# ESP_SIM7000V1_62.net
KiCad netlist of a schematic drawn in EAGLE
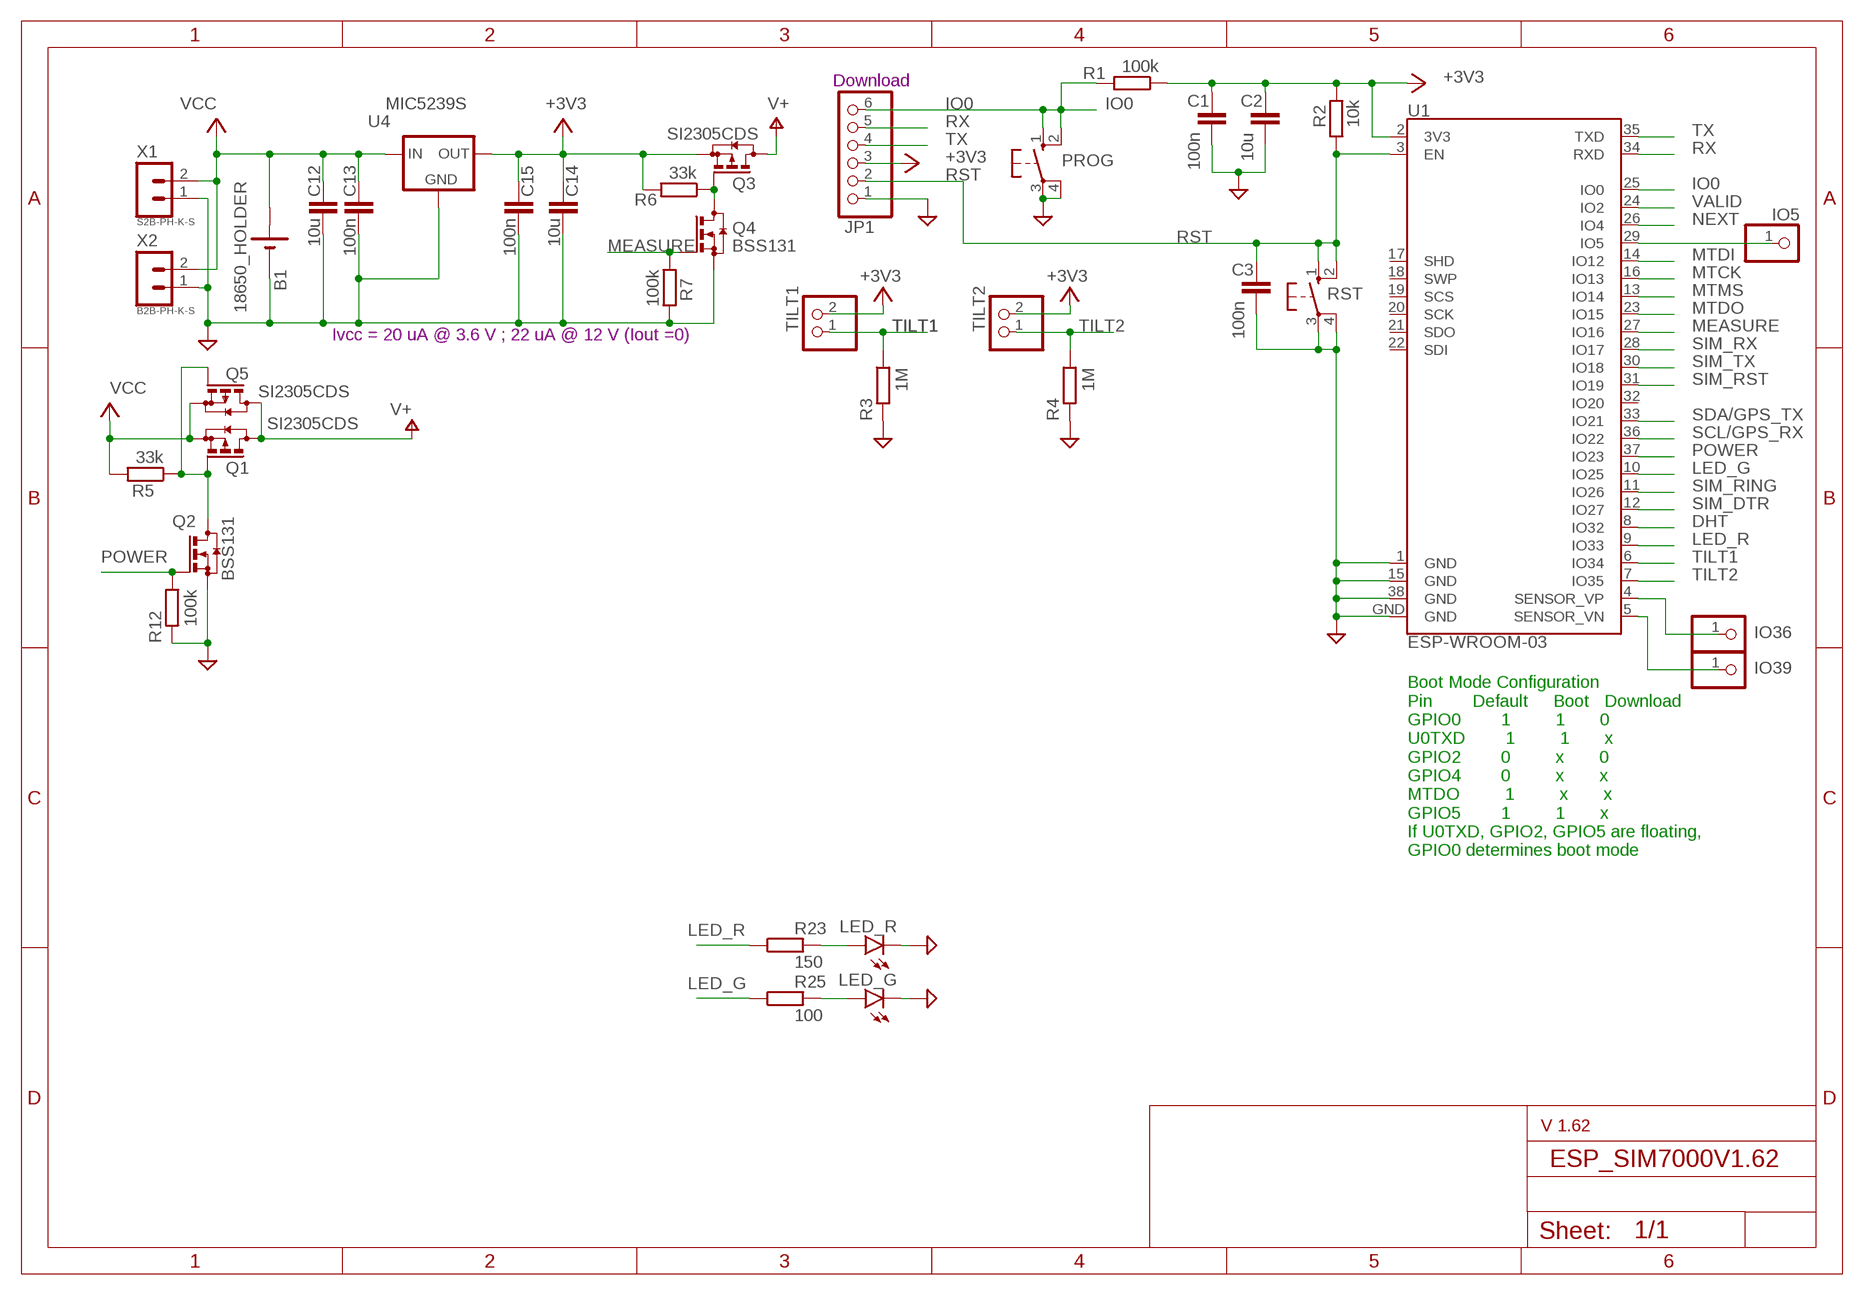
[diagram p0: schematic, sheet 1]

(export (version "E")
  (design (tool "Eeschema 10.0.6"))
  (components
    (comp (ref "B1")
      (value "18650_HOLDER")
      (footprint "eagle-import:18650")
      (libsource (lib "eagle-import") (part "18650_HOLDER"))
    )
    (comp (ref "C1")
      (value "100n")
      (footprint "eagle-import:C1206")
      (libsource (lib "eagle-import") (part "CC1206"))
    )
    (comp (ref "C2")
      (value "10u")
      (footprint "eagle-import:C1210")
      (libsource (lib "eagle-import") (part "CC1210"))
    )
    (comp (ref "C3")
      (value "100n")
      (footprint "eagle-import:C1206")
      (libsource (lib "eagle-import") (part "CC1206"))
    )
    (comp (ref "C12")
      (value "10u")
      (footprint "eagle-import:C1210")
      (libsource (lib "eagle-import") (part "CC1210"))
    )
    (comp (ref "C13")
      (value "100n")
      (footprint "eagle-import:C1206")
      (libsource (lib "eagle-import") (part "CC1206"))
    )
    (comp (ref "C14")
      (value "10u")
      (footprint "eagle-import:C1210")
      (libsource (lib "eagle-import") (part "CC1210"))
    )
    (comp (ref "C15")
      (value "100n")
      (footprint "eagle-import:C1206")
      (libsource (lib "eagle-import") (part "CC1206"))
    )
    (comp (ref "IO5")
      (value "PINHD-1X1")
      (footprint "eagle-import:1X01")
      (libsource (lib "eagle-import") (part "PINHD-1X1"))
    )
    (comp (ref "IO36")
      (value "PINHD-1X1")
      (footprint "eagle-import:1X01")
      (libsource (lib "eagle-import") (part "PINHD-1X1"))
    )
    (comp (ref "IO39")
      (value "PINHD-1X1")
      (footprint "eagle-import:1X01")
      (libsource (lib "eagle-import") (part "PINHD-1X1"))
    )
    (comp (ref "JP1")
      (value "PINHD-1X6")
      (footprint "eagle-import:1X06")
      (libsource (lib "eagle-import") (part "PINHD-1X6"))
    )
    (comp (ref "LED_G")
      (value "LEDSMT1206")
      (footprint "eagle-import:1206")
      (libsource (lib "eagle-import") (part "LEDSMT1206"))
    )
    (comp (ref "LED_R")
      (value "LEDSMT1206")
      (footprint "eagle-import:1206")
      (libsource (lib "eagle-import") (part "LEDSMT1206"))
    )
    (comp (ref "PROG")
      (value "10-XX")
      (footprint "eagle-import:B3F-10XX")
      (fields (field (name "MPN") "B3F-1000"))
      (libsource (lib "eagle-import") (part "10-XX"))
    )
    (comp (ref "Q1")
      (value "SI2305CDS")
      (footprint "eagle-import:SOT23")
      (libsource (lib "eagle-import") (part "SI2305CDS"))
    )
    (comp (ref "Q2")
      (value "BSS131")
      (footprint "eagle-import:SOT23")
      (libsource (lib "eagle-import") (part "BSS131"))
    )
    (comp (ref "Q3")
      (value "SI2305CDS")
      (footprint "eagle-import:SOT23")
      (libsource (lib "eagle-import") (part "SI2305CDS"))
    )
    (comp (ref "Q4")
      (value "BSS131")
      (footprint "eagle-import:SOT23")
      (libsource (lib "eagle-import") (part "BSS131"))
    )
    (comp (ref "Q5")
      (value "SI2305CDS")
      (footprint "eagle-import:SOT23")
      (libsource (lib "eagle-import") (part "SI2305CDS"))
    )
    (comp (ref "R1")
      (value "100k")
      (footprint "eagle-import:R1206")
      (libsource (lib "eagle-import") (part "RR1206"))
    )
    (comp (ref "R2")
      (value "10k")
      (footprint "eagle-import:R1206")
      (libsource (lib "eagle-import") (part "RR1206"))
    )
    (comp (ref "R3")
      (value "1M")
      (footprint "eagle-import:R1206")
      (libsource (lib "eagle-import") (part "RR1206"))
    )
    (comp (ref "R4")
      (value "1M")
      (footprint "eagle-import:R1206")
      (libsource (lib "eagle-import") (part "RR1206"))
    )
    (comp (ref "R5")
      (value "33k")
      (footprint "eagle-import:R1206")
      (libsource (lib "eagle-import") (part "RR1206"))
    )
    (comp (ref "R6")
      (value "33k")
      (footprint "eagle-import:R1206")
      (libsource (lib "eagle-import") (part "RR1206"))
    )
    (comp (ref "R7")
      (value "100k")
      (footprint "eagle-import:R1206")
      (libsource (lib "eagle-import") (part "RR1206"))
    )
    (comp (ref "R12")
      (value "100k")
      (footprint "eagle-import:R1206")
      (libsource (lib "eagle-import") (part "RR1206"))
    )
    (comp (ref "R23")
      (value "150")
      (footprint "eagle-import:R1206")
      (libsource (lib "eagle-import") (part "RR1206"))
    )
    (comp (ref "R25")
      (value "100")
      (footprint "eagle-import:R1206")
      (libsource (lib "eagle-import") (part "RR1206"))
    )
    (comp (ref "RST")
      (value "10-XX")
      (footprint "eagle-import:B3F-10XX")
      (fields (field (name "MPN") "B3F-1000"))
      (libsource (lib "eagle-import") (part "10-XX"))
    )
    (comp (ref "TILT1")
      (value "PINHD-1X2")
      (footprint "eagle-import:1X02")
      (libsource (lib "eagle-import") (part "PINHD-1X2"))
    )
    (comp (ref "TILT2")
      (value "PINHD-1X2")
      (footprint "eagle-import:1X02")
      (libsource (lib "eagle-import") (part "PINHD-1X2"))
    )
    (comp (ref "U1")
      (value "ESP-WROOM-03")
      (footprint "eagle-import:ESP-WROOM-03")
      (libsource (lib "eagle-import") (part "ESP-WROOM-03"))
    )
    (comp (ref "U4")
      (value "MIC5239S")
      (footprint "eagle-import:SOT223")
      (libsource (lib "eagle-import") (part "MIC5239S"))
    )
    (comp (ref "X1")
      (value "S2B-PH-K-S")
      (footprint "eagle-import:S2B-PH-K-S")
      (libsource (lib "eagle-import") (part "S2B-PH-K-S"))
    )
    (comp (ref "X2")
      (value "B2B-PH-K-S")
      (footprint "eagle-import:B2B-PH-K-S")
      (libsource (lib "eagle-import") (part "B2B-PH-K-S"))
    )
  )
  (nets
    (net (code "1") (name "+3V3") (class "Default")
      (node (ref "C1") (pin "1") (pinfunction "1_1") (pintype "passive"))
      (node (ref "C14") (pin "1") (pinfunction "1_1") (pintype "passive"))
      (node (ref "C15") (pin "1") (pinfunction "1_1") (pintype "passive"))
      (node (ref "C2") (pin "1") (pinfunction "1_1") (pintype "passive"))
      (node (ref "JP1") (pin "3") (pinfunction "3_3") (pintype "passive"))
      (node (ref "Q3") (pin "2") (pinfunction "S_2") (pintype "passive"))
      (node (ref "R1") (pin "1") (pinfunction "1_1") (pintype "passive"))
      (node (ref "R2") (pin "2") (pinfunction "2_2") (pintype "passive"))
      (node (ref "R6") (pin "2") (pinfunction "2_2") (pintype "passive"))
      (node (ref "TILT1") (pin "2") (pinfunction "2_2") (pintype "passive"))
      (node (ref "TILT2") (pin "2") (pinfunction "2_2") (pintype "passive"))
      (node (ref "U1") (pin "2") (pinfunction "3V3_2") (pintype "bidirectional"))
      (node (ref "U4") (pin "3") (pinfunction "OUT_3") (pintype "passive"))
    )
    (net (code "2") (name "/DHT") (class "Default")
      (node (ref "U1") (pin "8") (pinfunction "IO32_8") (pintype "bidirectional"))
    )
    (net (code "3") (name "/IO0") (class "Default")
      (node (ref "JP1") (pin "6") (pinfunction "6_6") (pintype "passive"))
      (node (ref "PROG") (pin "1") (pinfunction "S_1") (pintype "passive"))
      (node (ref "PROG") (pin "2") (pinfunction "S1_2") (pintype "passive"))
      (node (ref "R1") (pin "2") (pinfunction "2_2") (pintype "passive"))
      (node (ref "U1") (pin "25") (pinfunction "IO0_25") (pintype "bidirectional"))
    )
    (net (code "4") (name "/LED_G") (class "Default")
      (node (ref "R25") (pin "1") (pinfunction "1_1") (pintype "passive"))
      (node (ref "U1") (pin "10") (pinfunction "IO25_10") (pintype "bidirectional"))
    )
    (net (code "5") (name "/LED_R") (class "Default")
      (node (ref "R23") (pin "1") (pinfunction "1_1") (pintype "passive"))
      (node (ref "U1") (pin "9") (pinfunction "IO33_9") (pintype "bidirectional"))
    )
    (net (code "6") (name "/MEASURE") (class "Default")
      (node (ref "Q4") (pin "1") (pinfunction "G_1") (pintype "passive"))
      (node (ref "R7") (pin "1") (pinfunction "1_1") (pintype "passive"))
      (node (ref "U1") (pin "27") (pinfunction "IO16_27") (pintype "bidirectional"))
    )
    (net (code "7") (name "/MTCK") (class "Default")
      (node (ref "U1") (pin "16") (pinfunction "IO13_16") (pintype "bidirectional"))
    )
    (net (code "8") (name "/MTDI") (class "Default")
      (node (ref "U1") (pin "14") (pinfunction "IO12_14") (pintype "bidirectional"))
    )
    (net (code "9") (name "/MTDO") (class "Default")
      (node (ref "U1") (pin "23") (pinfunction "IO15_23") (pintype "bidirectional"))
    )
    (net (code "10") (name "/MTMS") (class "Default")
      (node (ref "U1") (pin "13") (pinfunction "IO14_13") (pintype "bidirectional"))
    )
    (net (code "11") (name "/NEXT") (class "Default")
      (node (ref "U1") (pin "26") (pinfunction "IO4_26") (pintype "bidirectional"))
    )
    (net (code "12") (name "/POWER") (class "Default")
      (node (ref "Q2") (pin "1") (pinfunction "G_1") (pintype "passive"))
      (node (ref "R12") (pin "1") (pinfunction "1_1") (pintype "passive"))
      (node (ref "U1") (pin "37") (pinfunction "IO23_37") (pintype "bidirectional"))
    )
    (net (code "13") (name "/RST") (class "Default")
      (node (ref "C3") (pin "1") (pinfunction "1_1") (pintype "passive"))
      (node (ref "JP1") (pin "2") (pinfunction "2_2") (pintype "passive"))
      (node (ref "R2") (pin "1") (pinfunction "1_1") (pintype "passive"))
      (node (ref "RST") (pin "1") (pinfunction "S_1") (pintype "passive"))
      (node (ref "RST") (pin "2") (pinfunction "S1_2") (pintype "passive"))
      (node (ref "U1") (pin "3") (pinfunction "EN_3") (pintype "bidirectional"))
    )
    (net (code "14") (name "/RX") (class "Default")
      (node (ref "JP1") (pin "5") (pinfunction "5_5") (pintype "passive"))
      (node (ref "U1") (pin "34") (pinfunction "RXD_34") (pintype "bidirectional"))
    )
    (net (code "15") (name "/SCL{slash}GPS_RX") (class "Default")
      (node (ref "U1") (pin "36") (pinfunction "IO22_36") (pintype "bidirectional"))
    )
    (net (code "16") (name "/SDA{slash}GPS_TX") (class "Default")
      (node (ref "U1") (pin "33") (pinfunction "IO21_33") (pintype "bidirectional"))
    )
    (net (code "17") (name "/SIM_DTR") (class "Default")
      (node (ref "U1") (pin "12") (pinfunction "IO27_12") (pintype "bidirectional"))
    )
    (net (code "18") (name "/SIM_RING") (class "Default")
      (node (ref "U1") (pin "11") (pinfunction "IO26_11") (pintype "bidirectional"))
    )
    (net (code "19") (name "/SIM_RST") (class "Default")
      (node (ref "U1") (pin "31") (pinfunction "IO19_31") (pintype "bidirectional"))
    )
    (net (code "20") (name "/SIM_RX") (class "Default")
      (node (ref "U1") (pin "28") (pinfunction "IO17_28") (pintype "bidirectional"))
    )
    (net (code "21") (name "/SIM_TX") (class "Default")
      (node (ref "U1") (pin "30") (pinfunction "IO18_30") (pintype "bidirectional"))
    )
    (net (code "22") (name "/TILT1") (class "Default")
      (node (ref "R3") (pin "1") (pinfunction "1_1") (pintype "passive"))
      (node (ref "TILT1") (pin "1") (pinfunction "1_1") (pintype "passive"))
      (node (ref "U1") (pin "6") (pinfunction "IO34_6") (pintype "bidirectional"))
    )
    (net (code "23") (name "/TILT2") (class "Default")
      (node (ref "R4") (pin "1") (pinfunction "1_1") (pintype "passive"))
      (node (ref "TILT2") (pin "1") (pinfunction "1_1") (pintype "passive"))
      (node (ref "U1") (pin "7") (pinfunction "IO35_7") (pintype "bidirectional"))
    )
    (net (code "24") (name "/TX") (class "Default")
      (node (ref "JP1") (pin "4") (pinfunction "4_4") (pintype "passive"))
      (node (ref "U1") (pin "35") (pinfunction "TXD_35") (pintype "bidirectional"))
    )
    (net (code "25") (name "/VALID") (class "Default")
      (node (ref "U1") (pin "24") (pinfunction "IO2_24") (pintype "bidirectional"))
    )
    (net (code "26") (name "GND") (class "Default")
      (node (ref "B1") (pin "-") (pinfunction "-_-") (pintype "passive"))
      (node (ref "C1") (pin "2") (pinfunction "2_2") (pintype "passive"))
      (node (ref "C12") (pin "2") (pinfunction "2_2") (pintype "passive"))
      (node (ref "C13") (pin "2") (pinfunction "2_2") (pintype "passive"))
      (node (ref "C14") (pin "2") (pinfunction "2_2") (pintype "passive"))
      (node (ref "C15") (pin "2") (pinfunction "2_2") (pintype "passive"))
      (node (ref "C2") (pin "2") (pinfunction "2_2") (pintype "passive"))
      (node (ref "C3") (pin "2") (pinfunction "2_2") (pintype "passive"))
      (node (ref "JP1") (pin "1") (pinfunction "1_1") (pintype "passive"))
      (node (ref "LED_G") (pin "C") (pinfunction "C_C") (pintype "passive"))
      (node (ref "LED_R") (pin "C") (pinfunction "C_C") (pintype "passive"))
      (node (ref "PROG") (pin "3") (pinfunction "P_3") (pintype "passive"))
      (node (ref "PROG") (pin "4") (pinfunction "P1_4") (pintype "passive"))
      (node (ref "Q2") (pin "2") (pinfunction "S_2") (pintype "passive"))
      (node (ref "Q4") (pin "2") (pinfunction "S_2") (pintype "passive"))
      (node (ref "R12") (pin "2") (pinfunction "2_2") (pintype "passive"))
      (node (ref "R3") (pin "2") (pinfunction "2_2") (pintype "passive"))
      (node (ref "R4") (pin "2") (pinfunction "2_2") (pintype "passive"))
      (node (ref "R7") (pin "2") (pinfunction "2_2") (pintype "passive"))
      (node (ref "RST") (pin "3") (pinfunction "P_3") (pintype "passive"))
      (node (ref "RST") (pin "4") (pinfunction "P1_4") (pintype "passive"))
      (node (ref "U1") (pin "1") (pinfunction "GND_1") (pintype "bidirectional"))
      (node (ref "U1") (pin "15") (pinfunction "GND_15") (pintype "bidirectional"))
      (node (ref "U1") (pin "38") (pinfunction "GND_38") (pintype "bidirectional"))
      (node (ref "U1") (pin "GND") (pinfunction "GND_GND") (pintype "bidirectional"))
      (node (ref "U4") (pin "2") (pinfunction "GND_2") (pintype "passive"))
      (node (ref "U4") (pin "4") (pinfunction "GND_4") (pintype "passive"))
      (node (ref "X1") (pin "1") (pinfunction "1_1") (pintype "passive"))
      (node (ref "X2") (pin "1") (pinfunction "1_1") (pintype "passive"))
    )
    (net (code "27") (name "Net-(LED_G-PadA)") (class "Default")
      (node (ref "LED_G") (pin "A") (pinfunction "A_A") (pintype "passive"))
      (node (ref "R25") (pin "2") (pinfunction "2_2") (pintype "passive"))
    )
    (net (code "28") (name "Net-(LED_R-PadA)") (class "Default")
      (node (ref "LED_R") (pin "A") (pinfunction "A_A") (pintype "passive"))
      (node (ref "R23") (pin "2") (pinfunction "2_2") (pintype "passive"))
    )
    (net (code "29") (name "Net-(Q1-G)") (class "Default")
      (node (ref "Q1") (pin "1") (pinfunction "G_1") (pintype "passive"))
      (node (ref "Q2") (pin "3") (pinfunction "D_3") (pintype "passive"))
      (node (ref "Q5") (pin "1") (pinfunction "G_1") (pintype "passive"))
      (node (ref "R5") (pin "1") (pinfunction "1_1") (pintype "passive"))
    )
    (net (code "30") (name "Net-(Q3-G)") (class "Default")
      (node (ref "Q3") (pin "1") (pinfunction "G_1") (pintype "passive"))
      (node (ref "Q4") (pin "3") (pinfunction "D_3") (pintype "passive"))
      (node (ref "R6") (pin "1") (pinfunction "1_1") (pintype "passive"))
    )
    (net (code "31") (name "Net-(U1-IO5)") (class "Default")
      (node (ref "IO5") (pin "1") (pinfunction "1_1") (pintype "passive"))
      (node (ref "U1") (pin "29") (pinfunction "IO5_29") (pintype "bidirectional"))
    )
    (net (code "32") (name "Net-(U1-SENSOR_VN)") (class "Default")
      (node (ref "IO39") (pin "1") (pinfunction "1_1") (pintype "passive"))
      (node (ref "U1") (pin "5") (pinfunction "SENSOR_VN_5") (pintype "bidirectional"))
    )
    (net (code "33") (name "Net-(U1-SENSOR_VP)") (class "Default")
      (node (ref "IO36") (pin "1") (pinfunction "1_1") (pintype "passive"))
      (node (ref "U1") (pin "4") (pinfunction "SENSOR_VP_4") (pintype "bidirectional"))
    )
    (net (code "34") (name "V+") (class "Default")
      (node (ref "Q1") (pin "3") (pinfunction "D_3") (pintype "passive"))
      (node (ref "Q3") (pin "3") (pinfunction "D_3") (pintype "passive"))
      (node (ref "Q5") (pin "3") (pinfunction "D_3") (pintype "passive"))
    )
    (net (code "35") (name "VCC") (class "Default")
      (node (ref "B1") (pin "+") (pinfunction "+_+") (pintype "passive"))
      (node (ref "C12") (pin "1") (pinfunction "1_1") (pintype "passive"))
      (node (ref "C13") (pin "1") (pinfunction "1_1") (pintype "passive"))
      (node (ref "Q1") (pin "2") (pinfunction "S_2") (pintype "passive"))
      (node (ref "Q5") (pin "2") (pinfunction "S_2") (pintype "passive"))
      (node (ref "R5") (pin "2") (pinfunction "2_2") (pintype "passive"))
      (node (ref "U4") (pin "1") (pinfunction "IN_1") (pintype "input"))
      (node (ref "X1") (pin "2") (pinfunction "2_2") (pintype "passive"))
      (node (ref "X2") (pin "2") (pinfunction "2_2") (pintype "passive"))
    )
    (net (code "36") (name "unconnected-(U1-IO20-Pad32)") (class "Default")
      (node (ref "U1") (pin "32") (pinfunction "IO20_32") (pintype "bidirectional"))
    )
    (net (code "37") (name "unconnected-(U1-SCK-Pad20)") (class "Default")
      (node (ref "U1") (pin "20") (pinfunction "SCK_20") (pintype "bidirectional"))
    )
    (net (code "38") (name "unconnected-(U1-SCS-Pad19)") (class "Default")
      (node (ref "U1") (pin "19") (pinfunction "SCS_19") (pintype "bidirectional"))
    )
    (net (code "39") (name "unconnected-(U1-SDI-Pad22)") (class "Default")
      (node (ref "U1") (pin "22") (pinfunction "SDI_22") (pintype "bidirectional"))
    )
    (net (code "40") (name "unconnected-(U1-SDO-Pad21)") (class "Default")
      (node (ref "U1") (pin "21") (pinfunction "SDO_21") (pintype "bidirectional"))
    )
    (net (code "41") (name "unconnected-(U1-SHD-Pad17)") (class "Default")
      (node (ref "U1") (pin "17") (pinfunction "SHD_17") (pintype "bidirectional"))
    )
    (net (code "42") (name "unconnected-(U1-SWP-Pad18)") (class "Default")
      (node (ref "U1") (pin "18") (pinfunction "SWP_18") (pintype "bidirectional"))
    )
  )
)
